# lm317_ic.net
KiCad netlist of a schematic drawn in EAGLE
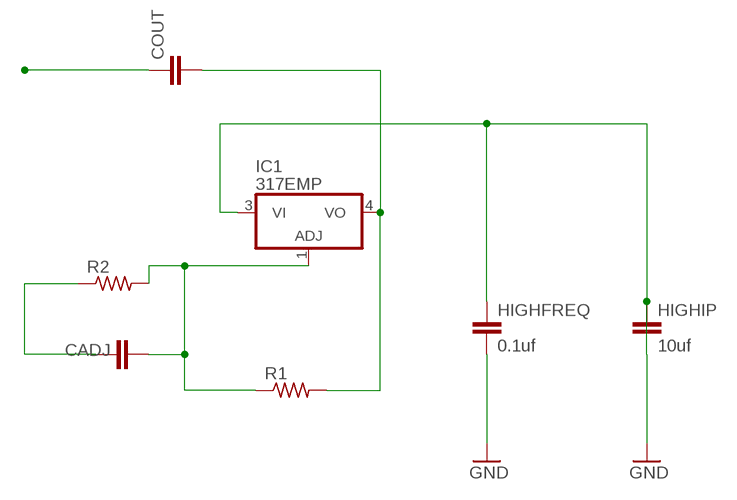
[diagram p0: schematic, sheet 1]

(export (version "E")
  (design (tool "Eeschema 10.0.6"))
  (components
    (comp (ref "CADJ")
      (value "C2,5-3")
      (footprint "eagle-import:C2.5-3")
      (libsource (lib "eagle-import") (part "C2,5-3"))
    )
    (comp (ref "COUT")
      (value "C2,5-3")
      (footprint "eagle-import:C2.5-3")
      (libsource (lib "eagle-import") (part "C2,5-3"))
    )
    (comp (ref "HIGHFREQ")
      (value "0.1uf")
      (footprint "eagle-import:C2.5-3")
      (libsource (lib "eagle-import") (part "C2,5-3"))
    )
    (comp (ref "HIGHIP")
      (value "10uf")
      (footprint "eagle-import:C2.5-3")
      (libsource (lib "eagle-import") (part "C2,5-3"))
    )
    (comp (ref "IC1")
      (value "317EMP")
      (footprint "eagle-import:SOT223")
      (libsource (lib "eagle-import") (part "317EMP"))
    )
    (comp (ref "R1")
      (value "R-US_0204/2V")
      (footprint "eagle-import:0204V")
      (libsource (lib "eagle-import") (part "R-US_0204/2V"))
    )
    (comp (ref "R2")
      (value "R-US_0204/2V")
      (footprint "eagle-import:0204V")
      (libsource (lib "eagle-import") (part "R-US_0204/2V"))
    )
  )
  (nets
    (net (code "1") (name "GND") (class "Default")
      (node (ref "HIGHFREQ") (pin "1") (pinfunction "1_1") (pintype "passive"))
      (node (ref "HIGHFREQ") (pin "2") (pinfunction "2_2") (pintype "passive"))
      (node (ref "HIGHIP") (pin "1") (pinfunction "1_1") (pintype "passive"))
      (node (ref "HIGHIP") (pin "2") (pinfunction "2_2") (pintype "passive"))
      (node (ref "IC1") (pin "3") (pinfunction "VI_3") (pintype "input"))
    )
    (net (code "2") (name "Net-(CADJ-Pad1)") (class "Default")
      (node (ref "CADJ") (pin "1") (pinfunction "1_1") (pintype "passive"))
      (node (ref "R2") (pin "1") (pinfunction "1_1") (pintype "passive"))
    )
    (net (code "3") (name "Net-(IC1-ADJ)") (class "Default")
      (node (ref "CADJ") (pin "2") (pinfunction "2_2") (pintype "passive"))
      (node (ref "IC1") (pin "1") (pinfunction "ADJ_1") (pintype "input"))
      (node (ref "R1") (pin "1") (pinfunction "1_1") (pintype "passive"))
      (node (ref "R2") (pin "2") (pinfunction "2_2") (pintype "passive"))
    )
    (net (code "4") (name "Net-(IC1-VO)") (class "Default")
      (node (ref "COUT") (pin "2") (pinfunction "2_2") (pintype "passive"))
      (node (ref "IC1") (pin "4") (pinfunction "VO_4") (pintype "passive"))
      (node (ref "R1") (pin "2") (pinfunction "2_2") (pintype "passive"))
    )
    (net (code "5") (name "unconnected-(COUT-Pad1)") (class "Default")
      (node (ref "COUT") (pin "1") (pinfunction "1_1") (pintype "passive"))
    )
  )
)
